# MotorDriversUnit.net
KiCad netlist of a schematic drawn in Altium Designer
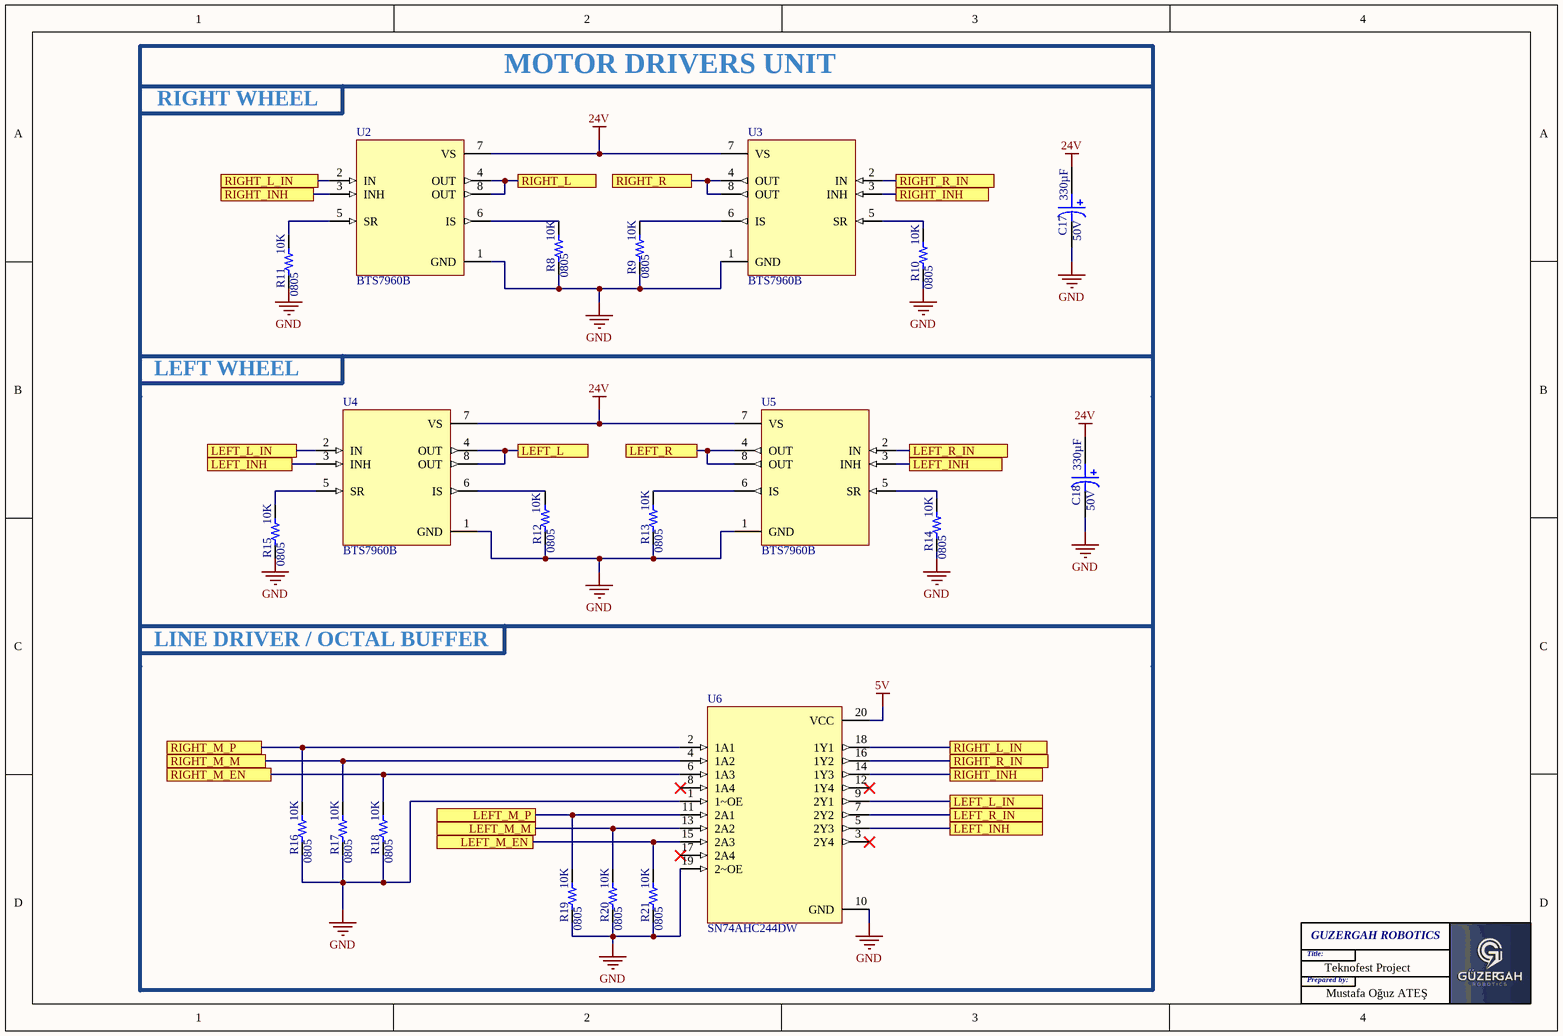
[diagram p0: MotorDriversUnit.SchDoc]

(export (version "E")
  (design (tool "Eeschema 10.0.6"))
  (components
    (comp (ref "C17")
      (value "330µF")
      (footprint "CAP_ALUM_330uF_10x17 5MM")
      (description "CAP.EL.330UF 50V 10x17 5MM 105C")
      (fields (field (name "VOLTAGE - RATED") "50V") (field (name "Comment") "CD11GCL-50V330-10X17"))
      (libsource (lib "TeknoFest") (part "CAP_ALUM_330uF_TH"))
    )
    (comp (ref "C18")
      (value "330µF")
      (footprint "CAP_ALUM_330uF_10x17 5MM")
      (description "CAP.EL.330UF 50V 10x17 5MM 105C")
      (fields (field (name "VOLTAGE - RATED") "50V") (field (name "Comment") "CD11GCL-50V330-10X17"))
      (libsource (lib "TeknoFest") (part "CAP_ALUM_330uF_TH"))
    )
    (comp (ref "R8")
      (value "10K")
      (footprint "RES_0805_10K")
      (description "RES 0805 10K ohm")
      (fields (field (name "PACKAGE / CASE") "0805") (field (name "Comment") "RES_0805_10K"))
      (libsource (lib "TeknoFest") (part "RES_0805_10K"))
    )
    (comp (ref "R9")
      (value "10K")
      (footprint "RES_0805_10K")
      (description "RES 0805 10K ohm")
      (fields (field (name "PACKAGE / CASE") "0805") (field (name "Comment") "RES_0805_10K"))
      (libsource (lib "TeknoFest") (part "RES_0805_10K"))
    )
    (comp (ref "R10")
      (value "10K")
      (footprint "RES_0805_10K")
      (description "RES 0805 10K ohm")
      (fields (field (name "PACKAGE / CASE") "0805") (field (name "Comment") "RES_0805_10K"))
      (libsource (lib "TeknoFest") (part "RES_0805_10K"))
    )
    (comp (ref "R11")
      (value "10K")
      (footprint "RES_0805_10K")
      (description "RES 0805 10K ohm")
      (fields (field (name "PACKAGE / CASE") "0805") (field (name "Comment") "RES_0805_10K"))
      (libsource (lib "TeknoFest") (part "RES_0805_10K"))
    )
    (comp (ref "R12")
      (value "10K")
      (footprint "RES_0805_10K")
      (description "RES 0805 10K ohm")
      (fields (field (name "PACKAGE / CASE") "0805") (field (name "Comment") "RES_0805_10K"))
      (libsource (lib "TeknoFest") (part "RES_0805_10K"))
    )
    (comp (ref "R13")
      (value "10K")
      (footprint "RES_0805_10K")
      (description "RES 0805 10K ohm")
      (fields (field (name "PACKAGE / CASE") "0805") (field (name "Comment") "RES_0805_10K"))
      (libsource (lib "TeknoFest") (part "RES_0805_10K"))
    )
    (comp (ref "R14")
      (value "10K")
      (footprint "RES_0805_10K")
      (description "RES 0805 10K ohm")
      (fields (field (name "PACKAGE / CASE") "0805") (field (name "Comment") "RES_0805_10K"))
      (libsource (lib "TeknoFest") (part "RES_0805_10K"))
    )
    (comp (ref "R15")
      (value "10K")
      (footprint "RES_0805_10K")
      (description "RES 0805 10K ohm")
      (fields (field (name "PACKAGE / CASE") "0805") (field (name "Comment") "RES_0805_10K"))
      (libsource (lib "TeknoFest") (part "RES_0805_10K"))
    )
    (comp (ref "R16")
      (value "10K")
      (footprint "RES_0805_10K")
      (description "RES 0805 10K ohm")
      (fields (field (name "PACKAGE / CASE") "0805") (field (name "Comment") "RES_0805_10K"))
      (libsource (lib "TeknoFest") (part "RES_0805_10K"))
    )
    (comp (ref "R17")
      (value "10K")
      (footprint "RES_0805_10K")
      (description "RES 0805 10K ohm")
      (fields (field (name "PACKAGE / CASE") "0805") (field (name "Comment") "RES_0805_10K"))
      (libsource (lib "TeknoFest") (part "RES_0805_10K"))
    )
    (comp (ref "R18")
      (value "10K")
      (footprint "RES_0805_10K")
      (description "RES 0805 10K ohm")
      (fields (field (name "PACKAGE / CASE") "0805") (field (name "Comment") "RES_0805_10K"))
      (libsource (lib "TeknoFest") (part "RES_0805_10K"))
    )
    (comp (ref "R19")
      (value "10K")
      (footprint "RES_0805_10K")
      (description "RES 0805 10K ohm")
      (fields (field (name "PACKAGE / CASE") "0805") (field (name "Comment") "RES_0805_10K"))
      (libsource (lib "TeknoFest") (part "RES_0805_10K"))
    )
    (comp (ref "R20")
      (value "10K")
      (footprint "RES_0805_10K")
      (description "RES 0805 10K ohm")
      (fields (field (name "PACKAGE / CASE") "0805") (field (name "Comment") "RES_0805_10K"))
      (libsource (lib "TeknoFest") (part "RES_0805_10K"))
    )
    (comp (ref "R21")
      (value "10K")
      (footprint "RES_0805_10K")
      (description "RES 0805 10K ohm")
      (fields (field (name "PACKAGE / CASE") "0805") (field (name "Comment") "RES_0805_10K"))
      (libsource (lib "TeknoFest") (part "RES_0805_10K"))
    )
    (comp (ref "U2")
      (value "BTS7960B")
      (footprint "DPAK127P1490X440-8N")
      (libsource (lib "TeknoFest") (part "BTS7960B"))
    )
    (comp (ref "U3")
      (value "BTS7960B")
      (footprint "DPAK127P1490X440-8N")
      (libsource (lib "") (part "BTS7960B_1"))
    )
    (comp (ref "U4")
      (value "BTS7960B")
      (footprint "DPAK127P1490X440-8N")
      (libsource (lib "TeknoFest") (part "BTS7960B"))
    )
    (comp (ref "U5")
      (value "BTS7960B")
      (footprint "DPAK127P1490X440-8N")
      (libsource (lib "") (part "BTS7960B_1"))
    )
    (comp (ref "U6")
      (value "SN74AHC244DW")
      (footprint "SOIC-20")
      (description "Buffer, Non-Inverting 2 Element 4 Bit per Element 3-State Output 20-SOIC")
      (libsource (lib "TeknoFest") (part "SN74AHC244DW"))
    )
  )
  (nets
    (net (code "1") (name "/LEFT_INH") (class "Default")
      (node (ref "U4") (pin "3") (pinfunction "INH_3") (pintype "input"))
      (node (ref "U5") (pin "3") (pinfunction "INH_3") (pintype "input"))
      (node (ref "U6") (pin "5") (pinfunction "2Y3_5") (pintype "output"))
    )
    (net (code "2") (name "/LEFT_L") (class "Default")
      (node (ref "U4") (pin "4") (pinfunction "OUT_4") (pintype "output"))
      (node (ref "U4") (pin "8") (pinfunction "OUT_8") (pintype "output"))
    )
    (net (code "3") (name "/LEFT_L_IN") (class "Default")
      (node (ref "U4") (pin "2") (pinfunction "IN_2") (pintype "input"))
      (node (ref "U6") (pin "9") (pinfunction "2Y1_9") (pintype "output"))
    )
    (net (code "4") (name "/LEFT_M_EN") (class "Default")
      (node (ref "R21") (pin "2") (pinfunction "2_2") (pintype "passive"))
      (node (ref "U6") (pin "15") (pinfunction "2A3_15") (pintype "input"))
    )
    (net (code "5") (name "/LEFT_M_M") (class "Default")
      (node (ref "R20") (pin "2") (pinfunction "2_2") (pintype "passive"))
      (node (ref "U6") (pin "13") (pinfunction "2A2_13") (pintype "input"))
    )
    (net (code "6") (name "/LEFT_M_P") (class "Default")
      (node (ref "R19") (pin "2") (pinfunction "2_2") (pintype "passive"))
      (node (ref "U6") (pin "11") (pinfunction "2A1_11") (pintype "input"))
    )
    (net (code "7") (name "/LEFT_R") (class "Default")
      (node (ref "U5") (pin "4") (pinfunction "OUT_4") (pintype "output"))
      (node (ref "U5") (pin "8") (pinfunction "OUT_8") (pintype "output"))
    )
    (net (code "8") (name "/LEFT_R_IN") (class "Default")
      (node (ref "U5") (pin "2") (pinfunction "IN_2") (pintype "input"))
      (node (ref "U6") (pin "7") (pinfunction "2Y2_7") (pintype "output"))
    )
    (net (code "9") (name "/RIGHT_INH") (class "Default")
      (node (ref "U2") (pin "3") (pinfunction "INH_3") (pintype "input"))
      (node (ref "U3") (pin "3") (pinfunction "INH_3") (pintype "input"))
      (node (ref "U6") (pin "14") (pinfunction "1Y3_14") (pintype "output"))
    )
    (net (code "10") (name "/RIGHT_L") (class "Default")
      (node (ref "U2") (pin "4") (pinfunction "OUT_4") (pintype "output"))
      (node (ref "U2") (pin "8") (pinfunction "OUT_8") (pintype "output"))
    )
    (net (code "11") (name "/RIGHT_L_IN") (class "Default")
      (node (ref "U2") (pin "2") (pinfunction "IN_2") (pintype "input"))
      (node (ref "U6") (pin "18") (pinfunction "1Y1_18") (pintype "output"))
    )
    (net (code "12") (name "/RIGHT_M_EN") (class "Default")
      (node (ref "R18") (pin "2") (pinfunction "2_2") (pintype "passive"))
      (node (ref "U6") (pin "6") (pinfunction "1A3_6") (pintype "input"))
    )
    (net (code "13") (name "/RIGHT_M_M") (class "Default")
      (node (ref "R17") (pin "2") (pinfunction "2_2") (pintype "passive"))
      (node (ref "U6") (pin "4") (pinfunction "1A2_4") (pintype "input"))
    )
    (net (code "14") (name "/RIGHT_M_P") (class "Default")
      (node (ref "R16") (pin "2") (pinfunction "2_2") (pintype "passive"))
      (node (ref "U6") (pin "2") (pinfunction "1A1_2") (pintype "input"))
    )
    (net (code "15") (name "/RIGHT_R") (class "Default")
      (node (ref "U3") (pin "4") (pinfunction "OUT_4") (pintype "output"))
      (node (ref "U3") (pin "8") (pinfunction "OUT_8") (pintype "output"))
    )
    (net (code "16") (name "/RIGHT_R_IN") (class "Default")
      (node (ref "U3") (pin "2") (pinfunction "IN_2") (pintype "input"))
      (node (ref "U6") (pin "16") (pinfunction "1Y2_16") (pintype "output"))
    )
    (net (code "17") (name "5V") (class "Default")
      (node (ref "U6") (pin "20") (pinfunction "VCC_20") (pintype "power_in"))
    )
    (net (code "18") (name "24V") (class "Default")
      (node (ref "C17") (pin "1") (pinfunction "1_1") (pintype "passive"))
      (node (ref "C18") (pin "1") (pinfunction "1_1") (pintype "passive"))
      (node (ref "U2") (pin "7") (pinfunction "VS_7") (pintype "power_in"))
      (node (ref "U3") (pin "7") (pinfunction "VS_7") (pintype "power_in"))
      (node (ref "U4") (pin "7") (pinfunction "VS_7") (pintype "power_in"))
      (node (ref "U5") (pin "7") (pinfunction "VS_7") (pintype "power_in"))
    )
    (net (code "19") (name "GND") (class "Default")
      (node (ref "C17") (pin "2") (pinfunction "2_2") (pintype "passive"))
      (node (ref "C18") (pin "2") (pinfunction "2_2") (pintype "passive"))
      (node (ref "R10") (pin "1") (pinfunction "1_1") (pintype "passive"))
      (node (ref "R11") (pin "1") (pinfunction "1_1") (pintype "passive"))
      (node (ref "R12") (pin "1") (pinfunction "1_1") (pintype "passive"))
      (node (ref "R13") (pin "1") (pinfunction "1_1") (pintype "passive"))
      (node (ref "R14") (pin "1") (pinfunction "1_1") (pintype "passive"))
      (node (ref "R15") (pin "1") (pinfunction "1_1") (pintype "passive"))
      (node (ref "R16") (pin "1") (pinfunction "1_1") (pintype "passive"))
      (node (ref "R17") (pin "1") (pinfunction "1_1") (pintype "passive"))
      (node (ref "R18") (pin "1") (pinfunction "1_1") (pintype "passive"))
      (node (ref "R19") (pin "1") (pinfunction "1_1") (pintype "passive"))
      (node (ref "R20") (pin "1") (pinfunction "1_1") (pintype "passive"))
      (node (ref "R21") (pin "1") (pinfunction "1_1") (pintype "passive"))
      (node (ref "R8") (pin "1") (pinfunction "1_1") (pintype "passive"))
      (node (ref "R9") (pin "1") (pinfunction "1_1") (pintype "passive"))
      (node (ref "U2") (pin "1") (pinfunction "GND_1") (pintype "power_in"))
      (node (ref "U3") (pin "1") (pinfunction "GND_1") (pintype "power_in"))
      (node (ref "U4") (pin "1") (pinfunction "GND_1") (pintype "power_in"))
      (node (ref "U5") (pin "1") (pinfunction "GND_1") (pintype "power_in"))
      (node (ref "U6") (pin "1") (pinfunction "1~OE_1") (pintype "input"))
      (node (ref "U6") (pin "10") (pinfunction "GND_10") (pintype "power_in"))
      (node (ref "U6") (pin "19") (pinfunction "2~OE_19") (pintype "input"))
    )
    (net (code "20") (name "Net-(U2-IS)") (class "Default")
      (node (ref "R8") (pin "2") (pinfunction "2_2") (pintype "passive"))
      (node (ref "U2") (pin "6") (pinfunction "IS_6") (pintype "output"))
    )
    (net (code "21") (name "Net-(U2-SR)") (class "Default")
      (node (ref "R11") (pin "2") (pinfunction "2_2") (pintype "passive"))
      (node (ref "U2") (pin "5") (pinfunction "SR_5") (pintype "input"))
    )
    (net (code "22") (name "Net-(U3-IS)") (class "Default")
      (node (ref "R9") (pin "2") (pinfunction "2_2") (pintype "passive"))
      (node (ref "U3") (pin "6") (pinfunction "IS_6") (pintype "output"))
    )
    (net (code "23") (name "Net-(U3-SR)") (class "Default")
      (node (ref "R10") (pin "2") (pinfunction "2_2") (pintype "passive"))
      (node (ref "U3") (pin "5") (pinfunction "SR_5") (pintype "input"))
    )
    (net (code "24") (name "Net-(U4-IS)") (class "Default")
      (node (ref "R12") (pin "2") (pinfunction "2_2") (pintype "passive"))
      (node (ref "U4") (pin "6") (pinfunction "IS_6") (pintype "output"))
    )
    (net (code "25") (name "Net-(U4-SR)") (class "Default")
      (node (ref "R15") (pin "2") (pinfunction "2_2") (pintype "passive"))
      (node (ref "U4") (pin "5") (pinfunction "SR_5") (pintype "input"))
    )
    (net (code "26") (name "Net-(U5-IS)") (class "Default")
      (node (ref "R13") (pin "2") (pinfunction "2_2") (pintype "passive"))
      (node (ref "U5") (pin "6") (pinfunction "IS_6") (pintype "output"))
    )
    (net (code "27") (name "Net-(U5-SR)") (class "Default")
      (node (ref "R14") (pin "2") (pinfunction "2_2") (pintype "passive"))
      (node (ref "U5") (pin "5") (pinfunction "SR_5") (pintype "input"))
    )
    (net (code "28") (name "unconnected-(U6-1A4-Pad8)") (class "Default")
      (node (ref "U6") (pin "8") (pinfunction "1A4_8") (pintype "input+no_connect"))
    )
    (net (code "29") (name "unconnected-(U6-1Y4-Pad12)") (class "Default")
      (node (ref "U6") (pin "12") (pinfunction "1Y4_12") (pintype "output+no_connect"))
    )
    (net (code "30") (name "unconnected-(U6-2A4-Pad17)") (class "Default")
      (node (ref "U6") (pin "17") (pinfunction "2A4_17") (pintype "input+no_connect"))
    )
    (net (code "31") (name "unconnected-(U6-2Y4-Pad3)") (class "Default")
      (node (ref "U6") (pin "3") (pinfunction "2Y4_3") (pintype "output+no_connect"))
    )
  )
)
